# LabDuinoPorts.net
KiCad netlist of a schematic drawn in EAGLE
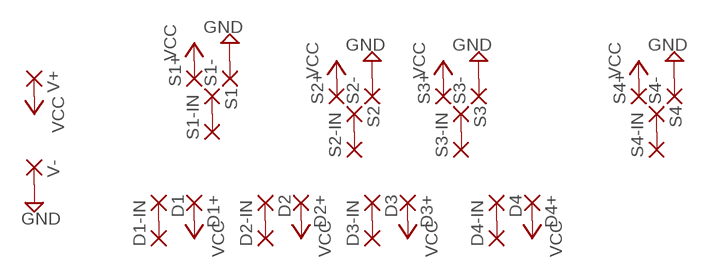
[diagram p0: schematic, sheet 1]

(export (version "E")
  (design (tool "Eeschema 10.0.6"))
  (components
    (comp (ref "D1")
      (value "2,54/0,9")
      (footprint "eagle-import:2,54_0,9")
      (libsource (lib "eagle-import") (part "2,54/0,9"))
    )
    (comp (ref "D1+")
      (value "2,54/0,9")
      (footprint "eagle-import:2,54_0,9")
      (libsource (lib "eagle-import") (part "2,54/0,9"))
    )
    (comp (ref "D1-IN")
      (value "2,54/0,9")
      (footprint "eagle-import:2,54_0,9")
      (libsource (lib "eagle-import") (part "2,54/0,9"))
    )
    (comp (ref "D2")
      (value "2,54/0,9")
      (footprint "eagle-import:2,54_0,9")
      (libsource (lib "eagle-import") (part "2,54/0,9"))
    )
    (comp (ref "D2+")
      (value "2,54/0,9")
      (footprint "eagle-import:2,54_0,9")
      (libsource (lib "eagle-import") (part "2,54/0,9"))
    )
    (comp (ref "D2-IN")
      (value "2,54/0,9")
      (footprint "eagle-import:2,54_0,9")
      (libsource (lib "eagle-import") (part "2,54/0,9"))
    )
    (comp (ref "D3")
      (value "2,54/0,9")
      (footprint "eagle-import:2,54_0,9")
      (libsource (lib "eagle-import") (part "2,54/0,9"))
    )
    (comp (ref "D3+")
      (value "2,54/0,9")
      (footprint "eagle-import:2,54_0,9")
      (libsource (lib "eagle-import") (part "2,54/0,9"))
    )
    (comp (ref "D3-IN")
      (value "2,54/0,9")
      (footprint "eagle-import:2,54_0,9")
      (libsource (lib "eagle-import") (part "2,54/0,9"))
    )
    (comp (ref "D4")
      (value "2,54/0,9")
      (footprint "eagle-import:2,54_0,9")
      (libsource (lib "eagle-import") (part "2,54/0,9"))
    )
    (comp (ref "D4+")
      (value "2,54/0,9")
      (footprint "eagle-import:2,54_0,9")
      (libsource (lib "eagle-import") (part "2,54/0,9"))
    )
    (comp (ref "D4-IN")
      (value "2,54/0,9")
      (footprint "eagle-import:2,54_0,9")
      (libsource (lib "eagle-import") (part "2,54/0,9"))
    )
    (comp (ref "S1")
      (value "2,54/0,9")
      (footprint "eagle-import:2,54_0,9")
      (libsource (lib "eagle-import") (part "2,54/0,9"))
    )
    (comp (ref "S1+")
      (value "2,54/0,9")
      (footprint "eagle-import:2,54_0,9")
      (libsource (lib "eagle-import") (part "2,54/0,9"))
    )
    (comp (ref "S1-")
      (value "2,54/0,9")
      (footprint "eagle-import:2,54_0,9")
      (libsource (lib "eagle-import") (part "2,54/0,9"))
    )
    (comp (ref "S1-IN")
      (value "2,54/0,9")
      (footprint "eagle-import:2,54_0,9")
      (libsource (lib "eagle-import") (part "2,54/0,9"))
    )
    (comp (ref "S2")
      (value "2,54/0,9")
      (footprint "eagle-import:2,54_0,9")
      (libsource (lib "eagle-import") (part "2,54/0,9"))
    )
    (comp (ref "S2+")
      (value "2,54/0,9")
      (footprint "eagle-import:2,54_0,9")
      (libsource (lib "eagle-import") (part "2,54/0,9"))
    )
    (comp (ref "S2-")
      (value "2,54/0,9")
      (footprint "eagle-import:2,54_0,9")
      (libsource (lib "eagle-import") (part "2,54/0,9"))
    )
    (comp (ref "S2-IN")
      (value "2,54/0,9")
      (footprint "eagle-import:2,54_0,9")
      (libsource (lib "eagle-import") (part "2,54/0,9"))
    )
    (comp (ref "S3")
      (value "2,54/0,9")
      (footprint "eagle-import:2,54_0,9")
      (libsource (lib "eagle-import") (part "2,54/0,9"))
    )
    (comp (ref "S3+")
      (value "2,54/0,9")
      (footprint "eagle-import:2,54_0,9")
      (libsource (lib "eagle-import") (part "2,54/0,9"))
    )
    (comp (ref "S3-")
      (value "2,54/0,9")
      (footprint "eagle-import:2,54_0,9")
      (libsource (lib "eagle-import") (part "2,54/0,9"))
    )
    (comp (ref "S3-IN")
      (value "2,54/0,9")
      (footprint "eagle-import:2,54_0,9")
      (libsource (lib "eagle-import") (part "2,54/0,9"))
    )
    (comp (ref "S4")
      (value "2,54/0,9")
      (footprint "eagle-import:2,54_0,9")
      (libsource (lib "eagle-import") (part "2,54/0,9"))
    )
    (comp (ref "S4+")
      (value "2,54/0,9")
      (footprint "eagle-import:2,54_0,9")
      (libsource (lib "eagle-import") (part "2,54/0,9"))
    )
    (comp (ref "S4-")
      (value "2,54/0,9")
      (footprint "eagle-import:2,54_0,9")
      (libsource (lib "eagle-import") (part "2,54/0,9"))
    )
    (comp (ref "S4-IN")
      (value "2,54/0,9")
      (footprint "eagle-import:2,54_0,9")
      (libsource (lib "eagle-import") (part "2,54/0,9"))
    )
    (comp (ref "V+")
      (value "2,54/0,9")
      (footprint "eagle-import:2,54_0,9")
      (libsource (lib "eagle-import") (part "2,54/0,9"))
    )
    (comp (ref "V-")
      (value "2,54/0,9")
      (footprint "eagle-import:2,54_0,9")
      (libsource (lib "eagle-import") (part "2,54/0,9"))
    )
  )
  (nets
    (net (code "1") (name "GND") (class "Default")
      (node (ref "S1-") (pin "1") (pinfunction "P_1") (pintype "passive"))
      (node (ref "S2-") (pin "1") (pinfunction "P_1") (pintype "passive"))
      (node (ref "S3-") (pin "1") (pinfunction "P_1") (pintype "passive"))
      (node (ref "S4-") (pin "1") (pinfunction "P_1") (pintype "passive"))
      (node (ref "V-") (pin "1") (pinfunction "P_1") (pintype "passive"))
    )
    (net (code "2") (name "Net-(D1-IN-P)") (class "Default")
      (node (ref "D1") (pin "1") (pinfunction "P_1") (pintype "passive"))
      (node (ref "D1-IN") (pin "1") (pinfunction "P_1") (pintype "passive"))
    )
    (net (code "3") (name "Net-(D2-IN-P)") (class "Default")
      (node (ref "D2") (pin "1") (pinfunction "P_1") (pintype "passive"))
      (node (ref "D2-IN") (pin "1") (pinfunction "P_1") (pintype "passive"))
    )
    (net (code "4") (name "Net-(D3-IN-P)") (class "Default")
      (node (ref "D3") (pin "1") (pinfunction "P_1") (pintype "passive"))
      (node (ref "D3-IN") (pin "1") (pinfunction "P_1") (pintype "passive"))
    )
    (net (code "5") (name "Net-(D4-IN-P)") (class "Default")
      (node (ref "D4") (pin "1") (pinfunction "P_1") (pintype "passive"))
      (node (ref "D4-IN") (pin "1") (pinfunction "P_1") (pintype "passive"))
    )
    (net (code "6") (name "Net-(S1-IN-P)") (class "Default")
      (node (ref "S1") (pin "1") (pinfunction "P_1") (pintype "passive"))
      (node (ref "S1-IN") (pin "1") (pinfunction "P_1") (pintype "passive"))
    )
    (net (code "7") (name "Net-(S2-IN-P)") (class "Default")
      (node (ref "S2") (pin "1") (pinfunction "P_1") (pintype "passive"))
      (node (ref "S2-IN") (pin "1") (pinfunction "P_1") (pintype "passive"))
    )
    (net (code "8") (name "Net-(S3-IN-P)") (class "Default")
      (node (ref "S3") (pin "1") (pinfunction "P_1") (pintype "passive"))
      (node (ref "S3-IN") (pin "1") (pinfunction "P_1") (pintype "passive"))
    )
    (net (code "9") (name "Net-(S4-IN-P)") (class "Default")
      (node (ref "S4") (pin "1") (pinfunction "P_1") (pintype "passive"))
      (node (ref "S4-IN") (pin "1") (pinfunction "P_1") (pintype "passive"))
    )
    (net (code "10") (name "VCC") (class "Default")
      (node (ref "D1+") (pin "1") (pinfunction "P_1") (pintype "passive"))
      (node (ref "D2+") (pin "1") (pinfunction "P_1") (pintype "passive"))
      (node (ref "D3+") (pin "1") (pinfunction "P_1") (pintype "passive"))
      (node (ref "D4+") (pin "1") (pinfunction "P_1") (pintype "passive"))
      (node (ref "S1+") (pin "1") (pinfunction "P_1") (pintype "passive"))
      (node (ref "S2+") (pin "1") (pinfunction "P_1") (pintype "passive"))
      (node (ref "S3+") (pin "1") (pinfunction "P_1") (pintype "passive"))
      (node (ref "S4+") (pin "1") (pinfunction "P_1") (pintype "passive"))
      (node (ref "V+") (pin "1") (pinfunction "P_1") (pintype "passive"))
    )
  )
)
